# hv_io_DCDC.net
KiCad netlist of a schematic drawn in Altium Designer
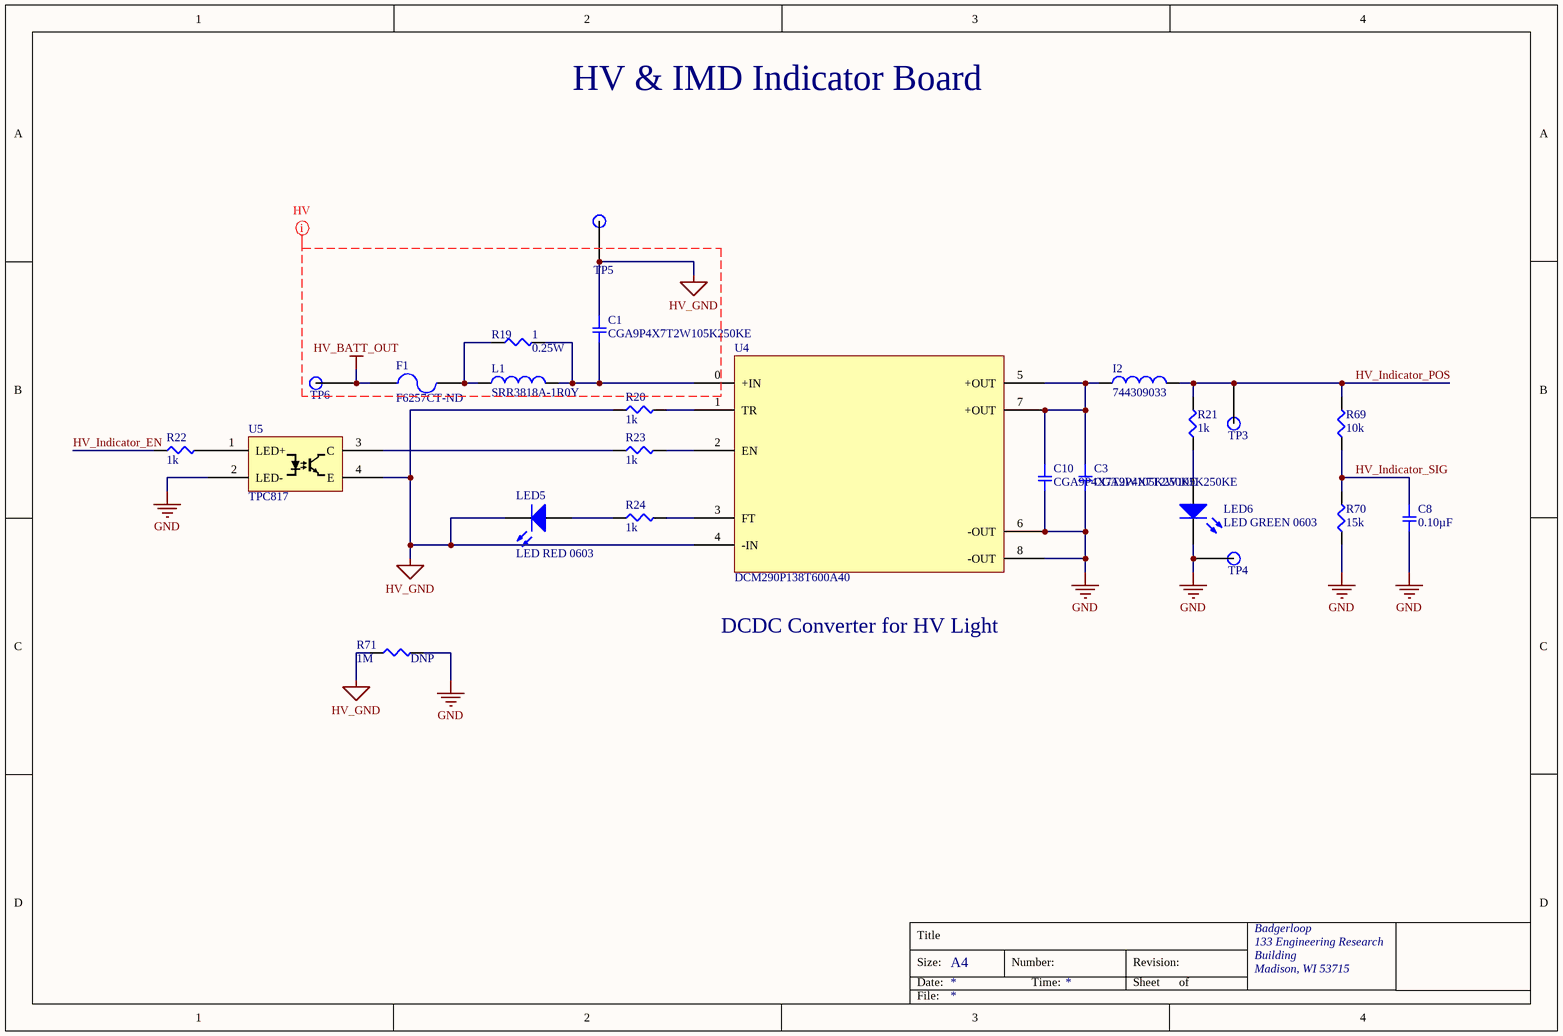
[diagram p0: hv_io_DCDC.SchDoc]

(export (version "E")
  (design (tool "Eeschema 10.0.6"))
  (components
    (comp (ref "C1")
      (value "CGA9P4X7T2W105K250KE")
      (footprint "CAPC8350X15N")
      (description "CAP CER 1UF 450V X7T 2220")
      (fields (field (name "MANUFACTURER") "TDK"))
      (libsource (lib "temp") (part "CGA9P4X7T2W105K250KE"))
    )
    (comp (ref "C3")
      (value "CGA9P4X7T2W105K250KE")
      (footprint "CAPC8350X15N")
      (description "CAP CER 1UF 450V X7T 2220")
      (fields (field (name "MANUFACTURER") "TDK"))
      (libsource (lib "temp") (part "CGA9P4X7T2W105K250KE"))
    )
    (comp (ref "C8")
      (value "0.10µF")
      (footprint "SMD-0805C")
      (description "CAP CER 0.1UF 50V X7R 0805")
      (fields
        (field (name "PART NUMBER") "GCD21BR71H104KA01L")
        (field (name "MANUFACTURER") "Murata Electronics North America")
      )
      (libsource (lib "altium-import") (part "root_0_GCD21BR71H104KA01L_"))
    )
    (comp (ref "C10")
      (value "CGA9P4X7T2W105K250KE")
      (footprint "CAPC8350X15N")
      (description "CAP CER 1UF 450V X7T 2220")
      (fields (field (name "MANUFACTURER") "TDK"))
      (libsource (lib "temp") (part "CGA9P4X7T2W105K250KE"))
    )
    (comp (ref "F1")
      (value "F6257CT-ND")
      (footprint "SMD-0805-RES")
      (description "FUSE BOARD MNT 500MA 350VAC/VDC")
      (fields (field (name "MANUFACTURER") "Littelfuse"))
      (libsource (lib "temp") (part "F6257CT-ND"))
    )
    (comp (ref "I2")
      (value "744309033")
      (footprint "INDM140130X90N")
      (description "FIXED IND 330NH 47.5A 0.165 MOHM")
      (fields (field (name "MANUFACTURER") "Wurth"))
      (libsource (lib "temp") (part "744309033"))
    )
    (comp (ref "L1")
      (value "SRR3818A-1R0Y")
      (footprint "INDM3838X18N")
      (description "FIXED IND 1UH 3.6A 37 MOHM SMD")
      (fields (field (name "MANUFACTURER") "Bourns Inc."))
      (libsource (lib "temp") (part "SRR3818A-1R0Y"))
    )
    (comp (ref "LED5")
      (value "LED RED 0603")
      (footprint "LED 0603 RED")
      (description "Red 631nm LED Indication - Discrete 2V 0603 (1608 Metric)")
      (fields (field (name "MANUFACTURER") "Lite-On Inc."))
      (libsource (lib "misc") (part "LED RED 0603"))
    )
    (comp (ref "LED6")
      (value "LED GREEN 0603")
      (footprint "LED 0603 GREEN")
      (fields (field (name "MANUFACTURER") "Lite-On Inc."))
      (libsource (lib "misc") (part "LED GREEN 0603"))
    )
    (comp (ref "R19")
      (value "1")
      (footprint "SMD-1206-RES")
      (description "RES SMD 1 OHM 1% 1/4W 1206")
      (fields
        (field (name "PART NUMBER") "ERJ-8RQF1R0V")
        (field (name "DIGI-KEY PART NUMBER") "P1.0RCT-ND")
        (field (name "POWER (WATTS)") "0.25W")
      )
      (libsource (lib "resistor") (part "ERJ-8RQF1R0V"))
    )
    (comp (ref "R20")
      (value "1k")
      (footprint "SMD-0805-RES")
      (description "RES SMD 1K OHM 1% 1/8W 0805")
      (fields
        (field (name "PART NUMBER") "ERJ-6ENF1001V")
        (field (name "DIGI-KEY PART NUMBER") "P1.00KCCT-ND")
      )
      (libsource (lib "resistor") (part "ERJ-6ENF1001V"))
    )
    (comp (ref "R21")
      (value "1k")
      (footprint "SMD-0805-RES")
      (description "RES SMD 1K OHM 1% 1/8W 0805")
      (fields
        (field (name "PART NUMBER") "ERJ-6ENF1001V")
        (field (name "DIGI-KEY PART NUMBER") "P1.00KCCT-ND")
      )
      (libsource (lib "resistor") (part "ERJ-6ENF1001V"))
    )
    (comp (ref "R22")
      (value "1k")
      (footprint "SMD-0805-RES")
      (description "RES SMD 1K OHM 1% 1/8W 0805")
      (fields
        (field (name "PART NUMBER") "ERJ-6ENF1001V")
        (field (name "DIGI-KEY PART NUMBER") "P1.00KCCT-ND")
      )
      (libsource (lib "resistor") (part "ERJ-6ENF1001V"))
    )
    (comp (ref "R23")
      (value "1k")
      (footprint "SMD-0805-RES")
      (description "RES SMD 1K OHM 1% 1/8W 0805")
      (fields
        (field (name "PART NUMBER") "ERJ-6ENF1001V")
        (field (name "DIGI-KEY PART NUMBER") "P1.00KCCT-ND")
      )
      (libsource (lib "resistor") (part "ERJ-6ENF1001V"))
    )
    (comp (ref "R24")
      (value "1k")
      (footprint "SMD-0805-RES")
      (description "RES SMD 1K OHM 1% 1/8W 0805")
      (fields
        (field (name "PART NUMBER") "ERJ-6ENF1001V")
        (field (name "DIGI-KEY PART NUMBER") "P1.00KCCT-ND")
      )
      (libsource (lib "resistor") (part "ERJ-6ENF1001V"))
    )
    (comp (ref "R69")
      (value "10k")
      (footprint "SMD-0805-RES")
      (description "RES SMD 10K OHM 5% 1/2W 0805")
      (fields (field (name "PART NUMBER") "ERJ-P06J103V") (field (name "DIGI-KEY PART NUMBER") "P10KADCT-ND"))
      (libsource (lib "altium-import") (part "root_1_ERJ-P06J103V_"))
    )
    (comp (ref "R70")
      (value "15k")
      (footprint "SMD-0805-RES")
      (description "RES SMD 15K OHM 5% 1/2W 0805")
      (fields (field (name "PART NUMBER") "ERJ-P06J153V") (field (name "DIGI-KEY PART NUMBER") "P15KADCT-ND"))
      (libsource (lib "altium-import") (part "root_1_ERJ-P06J153V_"))
    )
    (comp (ref "R71")
      (value "1M")
      (footprint "SMD-1206-RES")
      (description "RES SMD 1M OHM 5% 2/3W 1206")
      (fields
        (field (name "PART NUMBER") "ERJ-P08J105V")
        (field (name "DIGI-KEY PART NUMBER") "P1.0MALCT-ND")
        (field (name "DNP") "DNP")
      )
      (libsource (lib "resistor") (part "ERJ-P08J105V"))
    )
    (comp (ref "TP3") (value "TP") (footprint "Test Point") (libsource (lib "misc") (part "TP")))
    (comp (ref "TP4") (value "TP") (footprint "Test Point") (libsource (lib "misc") (part "TP")))
    (comp (ref "TP5") (value "TP") (footprint "Test Point") (libsource (lib "misc") (part "TP")))
    (comp (ref "TP6") (value "TP") (footprint "Test Point") (libsource (lib "misc") (part "TP")))
    (comp (ref "U4")
      (value "DCM290P138T600A40")
      (footprint "DCM290y138x600A40")
      (description "DC DC CONVERTER 13.8V 600W")
      (fields (field (name "MANUFACTURER") "Vicor"))
      (libsource (lib "ic") (part "DCM290P138T600A40"))
    )
    (comp (ref "U5")
      (value "TPC817")
      (footprint "SOT200P1005X328-5N")
      (description "OPTOISO 5KV TRANS 4SOP")
      (fields (field (name "MANUFACTURER") "Taiwan Semi"))
      (libsource (lib "ic") (part "TPC817"))
    )
  )
  (nets
    (net (code "2") (name "/HV_Indicator_EN") (class "Default")
      (node (ref "R22") (pin "1") (pinfunction "1_1") (pintype "passive"))
    )
    (net (code "3") (name "/HV_Indicator_POS") (class "Default")
      (node (ref "I2") (pin "2") (pinfunction "2_2") (pintype "passive"))
      (node (ref "R21") (pin "2") (pinfunction "2_2") (pintype "passive"))
      (node (ref "R69") (pin "2") (pinfunction "2_2") (pintype "passive"))
      (node (ref "TP3") (pin "1") (pinfunction "1_1") (pintype "passive"))
    )
    (net (code "4") (name "/HV_Indicator_SIG") (class "Default")
      (node (ref "C8") (pin "1") (pinfunction "1_1") (pintype "passive"))
      (node (ref "R69") (pin "1") (pinfunction "1_1") (pintype "passive"))
      (node (ref "R70") (pin "2") (pinfunction "2_2") (pintype "passive"))
    )
    (net (code "5") (name "GND") (class "Default")
      (node (ref "C10") (pin "2") (pinfunction "2_2") (pintype "passive"))
      (node (ref "C3") (pin "2") (pinfunction "2_2") (pintype "passive"))
      (node (ref "C8") (pin "2") (pinfunction "2_2") (pintype "passive"))
      (node (ref "LED6") (pin "2") (pinfunction "K_2") (pintype "passive"))
      (node (ref "R70") (pin "1") (pinfunction "1_1") (pintype "passive"))
      (node (ref "R71") (pin "2") (pinfunction "2_2") (pintype "passive"))
      (node (ref "TP4") (pin "1") (pinfunction "1_1") (pintype "passive"))
      (node (ref "U4") (pin "6") (pinfunction "-OUT_6") (pintype "passive"))
      (node (ref "U4") (pin "8") (pinfunction "-OUT_8") (pintype "passive"))
      (node (ref "U5") (pin "2") (pinfunction "LED-_2") (pintype "passive"))
    )
    (net (code "6") (name "HV_BATT_OUT") (class "Default")
      (node (ref "F1") (pin "1") (pinfunction "1_1") (pintype "passive"))
      (node (ref "TP6") (pin "1") (pinfunction "1_1") (pintype "passive"))
    )
    (net (code "7") (name "HV_GND") (class "Default")
      (node (ref "C1") (pin "1") (pinfunction "1_1") (pintype "passive"))
      (node (ref "LED5") (pin "2") (pinfunction "K_2") (pintype "passive"))
      (node (ref "R20") (pin "1") (pinfunction "1_1") (pintype "passive"))
      (node (ref "R71") (pin "1") (pinfunction "1_1") (pintype "passive"))
      (node (ref "TP5") (pin "1") (pinfunction "1_1") (pintype "passive"))
      (node (ref "U4") (pin "4") (pinfunction "-IN_4") (pintype "passive"))
      (node (ref "U5") (pin "4") (pinfunction "E_4") (pintype "passive"))
    )
    (net (code "8") (name "Net-(C10-Pad1)") (class "Default")
      (node (ref "C10") (pin "1") (pinfunction "1_1") (pintype "passive"))
      (node (ref "C3") (pin "1") (pinfunction "1_1") (pintype "passive"))
      (node (ref "I2") (pin "1") (pinfunction "1_1") (pintype "passive"))
      (node (ref "U4") (pin "5") (pinfunction "+OUT_5") (pintype "passive"))
      (node (ref "U4") (pin "7") (pinfunction "+OUT_7") (pintype "passive"))
    )
    (net (code "9") (name "Net-(F1-Pad2)") (class "Default")
      (node (ref "F1") (pin "2") (pinfunction "2_2") (pintype "passive"))
      (node (ref "L1") (pin "1") (pinfunction "1_1") (pintype "passive"))
      (node (ref "R19") (pin "1") (pinfunction "1_1") (pintype "passive"))
    )
    (net (code "10") (name "Net-(LED5-A)") (class "Default")
      (node (ref "LED5") (pin "1") (pinfunction "A_1") (pintype "passive"))
      (node (ref "R24") (pin "1") (pinfunction "1_1") (pintype "passive"))
    )
    (net (code "11") (name "Net-(LED6-A)") (class "Default")
      (node (ref "LED6") (pin "1") (pinfunction "A_1") (pintype "passive"))
      (node (ref "R21") (pin "1") (pinfunction "1_1") (pintype "passive"))
    )
    (net (code "12") (name "Net-(U4-+IN)") (class "Default")
      (node (ref "C1") (pin "2") (pinfunction "2_2") (pintype "passive"))
      (node (ref "L1") (pin "2") (pinfunction "2_2") (pintype "passive"))
      (node (ref "R19") (pin "2") (pinfunction "2_2") (pintype "passive"))
      (node (ref "U4") (pin "0") (pinfunction "+IN_0") (pintype "passive"))
    )
    (net (code "13") (name "Net-(U4-EN)") (class "Default")
      (node (ref "R23") (pin "2") (pinfunction "2_2") (pintype "passive"))
      (node (ref "U4") (pin "2") (pinfunction "EN_2") (pintype "passive"))
    )
    (net (code "14") (name "Net-(U4-FT)") (class "Default")
      (node (ref "R24") (pin "2") (pinfunction "2_2") (pintype "passive"))
      (node (ref "U4") (pin "3") (pinfunction "FT_3") (pintype "passive"))
    )
    (net (code "15") (name "Net-(U4-TR)") (class "Default")
      (node (ref "R20") (pin "2") (pinfunction "2_2") (pintype "passive"))
      (node (ref "U4") (pin "1") (pinfunction "TR_1") (pintype "passive"))
    )
    (net (code "16") (name "Net-(U5-C)") (class "Default")
      (node (ref "R23") (pin "1") (pinfunction "1_1") (pintype "passive"))
      (node (ref "U5") (pin "3") (pinfunction "C_3") (pintype "passive"))
    )
    (net (code "17") (name "Net-(U5-LED+)") (class "Default")
      (node (ref "R22") (pin "2") (pinfunction "2_2") (pintype "passive"))
      (node (ref "U5") (pin "1") (pinfunction "LED+_1") (pintype "passive"))
    )
  )
)
